# BW1092_LEVEL_SHIFT.net
KiCad netlist of a schematic drawn in Altium Designer
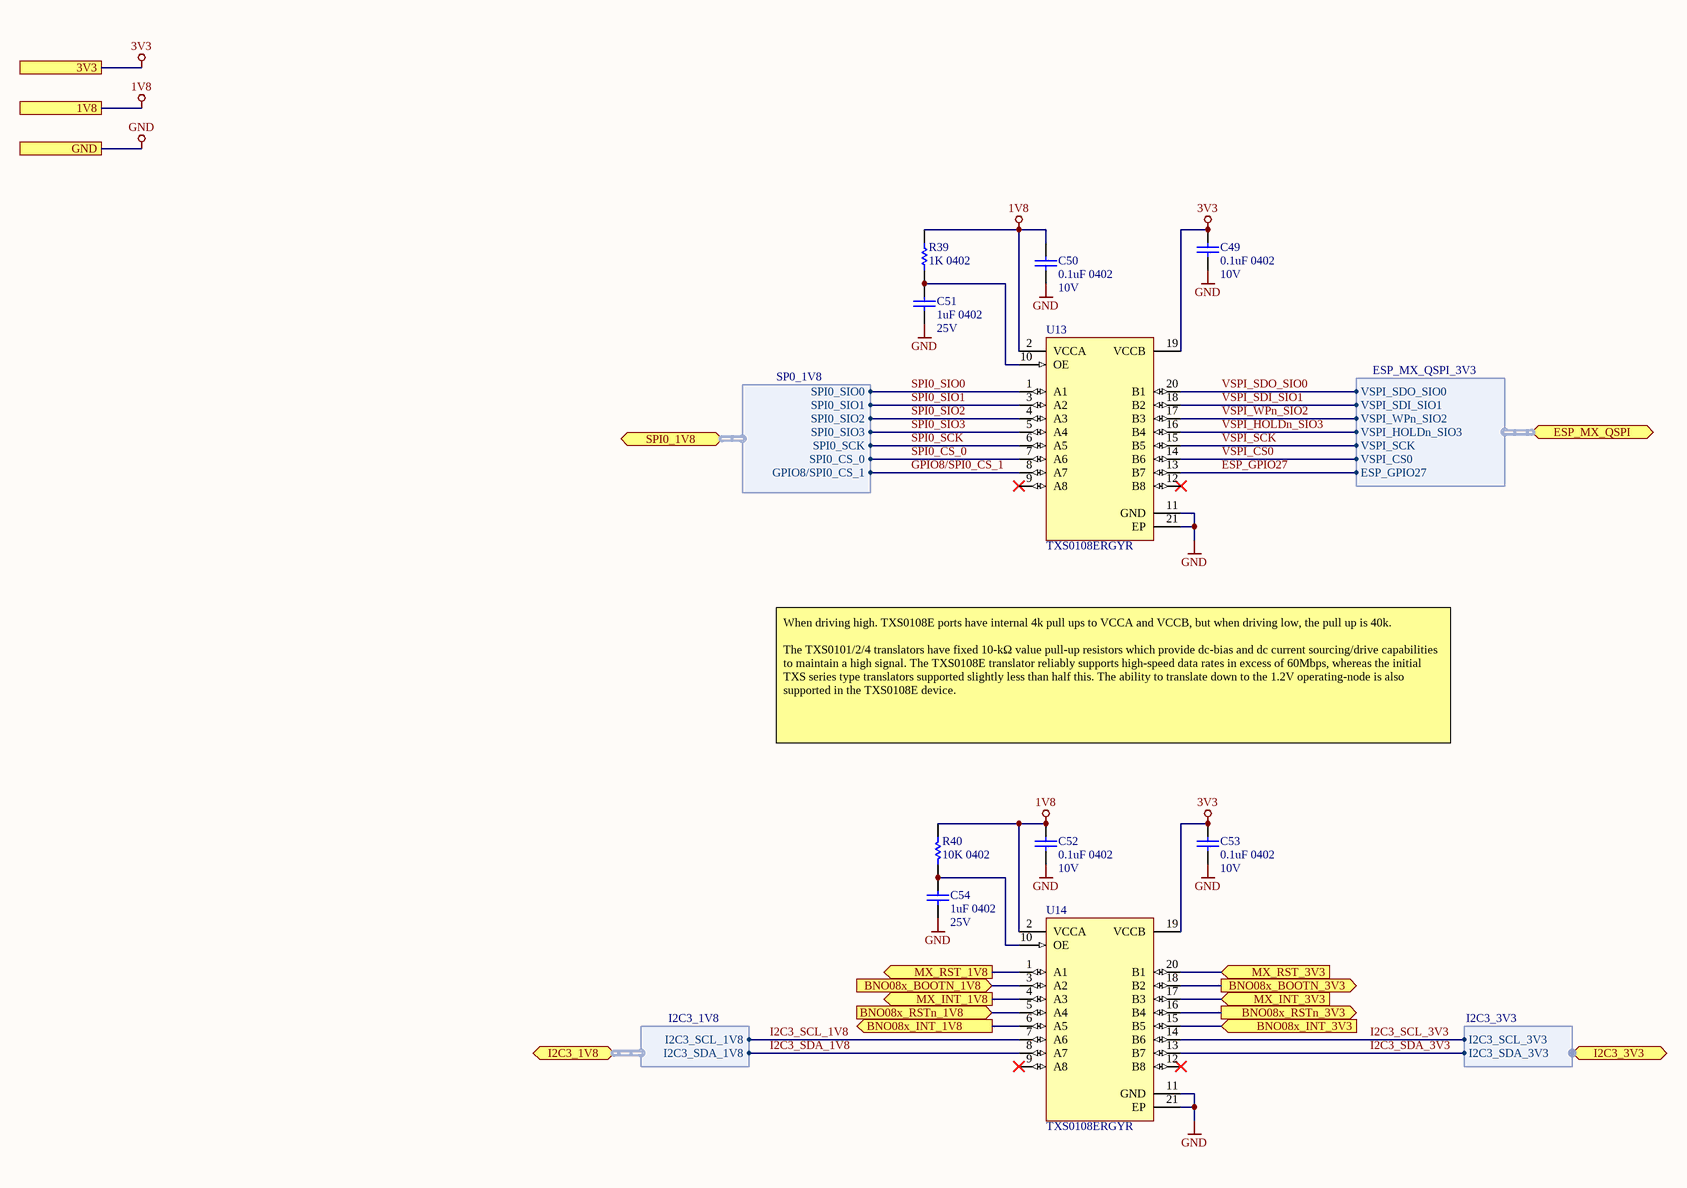
[diagram p0: BW1092_LEVEL_SHIFT.SchDoc]

(export (version "E")
  (design (tool "Eeschema 10.0.6"))
  (components
    (comp (ref "C49")
      (value "0.1uF 0402")
      (footprint "CAP_Altium_Vault_Generic:CAPC0402(1005)70_N")
      (description "CAP CER 0.1UF 10V X7R 0402 5%")
      (fields (field (name "TOLERANCE") "5%") (field (name "VOLTAGE RATING") "10V"))
      (libsource (lib "LuxonisMaster") (part "GRM155R71A104JA01D"))
    )
    (comp (ref "C50")
      (value "0.1uF 0402")
      (footprint "CAP_Altium_Vault_Generic:CAPC0402(1005)70_N")
      (description "CAP CER 0.1UF 10V X7R 0402 5%")
      (fields (field (name "TOLERANCE") "5%") (field (name "VOLTAGE RATING") "10V"))
      (libsource (lib "LuxonisMaster") (part "GRM155R71A104JA01D"))
    )
    (comp (ref "C51")
      (value "1uF 0402")
      (footprint "CAP_Altium_Vault_Generic:CAPC0402(1005)70_N")
      (description "CAP CER 1UF 25V X5R 0402 10%")
      (fields
        (field (name "TOLERANCE") "10%")
        (field (name "VOLTAGE") "25V")
        (field (name "VOLTAGE RATING") "25V")
      )
      (libsource (lib "LuxonisMaster") (part "GRM155R61E105KA12D"))
    )
    (comp (ref "C52")
      (value "0.1uF 0402")
      (footprint "CAP_Altium_Vault_Generic:CAPC0402(1005)70_N")
      (description "CAP CER 0.1UF 10V X7R 0402 5%")
      (fields (field (name "TOLERANCE") "5%") (field (name "VOLTAGE RATING") "10V"))
      (libsource (lib "LuxonisMaster") (part "GRM155R71A104JA01D"))
    )
    (comp (ref "C53")
      (value "0.1uF 0402")
      (footprint "CAP_Altium_Vault_Generic:CAPC0402(1005)70_N")
      (description "CAP CER 0.1UF 10V X7R 0402 5%")
      (fields (field (name "TOLERANCE") "5%") (field (name "VOLTAGE RATING") "10V"))
      (libsource (lib "LuxonisMaster") (part "GRM155R71A104JA01D"))
    )
    (comp (ref "C54")
      (value "1uF 0402")
      (footprint "CAP_Altium_Vault_Generic:CAPC0402(1005)70_N")
      (description "CAP CER 1UF 25V X5R 0402 10%")
      (fields
        (field (name "TOLERANCE") "10%")
        (field (name "VOLTAGE") "25V")
        (field (name "VOLTAGE RATING") "25V")
      )
      (libsource (lib "LuxonisMaster") (part "GRM155R61E105KA12D"))
    )
    (comp (ref "R39")
      (value "1K 0402")
      (footprint "RES_Altium_Vault_Generic:RESC0402(1005)_N")
      (fields (field (name "TOLERANCE") "1%"))
      (libsource (lib "LuxonisMaster") (part "RC0402FR-071KL"))
    )
    (comp (ref "R40")
      (value "10K 0402")
      (footprint "RES_Altium_Vault_Generic:RESC0402(1005)_N")
      (fields (field (name "TOLERANCE") "1%"))
      (libsource (lib "LuxonisMaster") (part "RC0402FR-1310KL"))
    )
    (comp (ref "U13")
      (value "TXS0108ERGYR")
      (footprint "BW1092_R0M0E0:TXS0108ERGYR")
      (description "IC TRNSLTR BIDIRECTIONAL 20VQFN")
      (libsource (lib "BW1092_R0M0E0") (part "TXS0108ERGYR"))
    )
    (comp (ref "U14")
      (value "TXS0108ERGYR")
      (footprint "BW1092_R0M0E0:TXS0108ERGYR")
      (description "IC TRNSLTR BIDIRECTIONAL 20VQFN")
      (libsource (lib "BW1092_R0M0E0") (part "TXS0108ERGYR"))
    )
  )
  (nets
    (net (code "5") (name "/BNO08x_BOOTN_1V8") (class "Default")
      (node (ref "U14") (pin "3") (pinfunction "A2_3") (pintype "bidirectional"))
    )
    (net (code "6") (name "/BNO08x_BOOTN_3V3") (class "Default")
      (node (ref "U14") (pin "18") (pinfunction "B2_18") (pintype "bidirectional"))
    )
    (net (code "7") (name "/BNO08x_INT_1V8") (class "Default")
      (node (ref "U14") (pin "6") (pinfunction "A5_6") (pintype "bidirectional"))
    )
    (net (code "8") (name "/BNO08x_INT_3V3") (class "Default")
      (node (ref "U14") (pin "15") (pinfunction "B5_15") (pintype "bidirectional"))
    )
    (net (code "9") (name "/BNO08x_RSTn_1V8") (class "Default")
      (node (ref "U14") (pin "5") (pinfunction "A4_5") (pintype "bidirectional"))
    )
    (net (code "10") (name "/BNO08x_RSTn_3V3") (class "Default")
      (node (ref "U14") (pin "16") (pinfunction "B4_16") (pintype "bidirectional"))
    )
    (net (code "11") (name "/ESP_GPIO27") (class "Default")
      (node (ref "U13") (pin "13") (pinfunction "B7_13") (pintype "bidirectional"))
    )
    (net (code "12") (name "/GPIO8{slash}SPI0_CS_1") (class "Default")
      (node (ref "U13") (pin "8") (pinfunction "A7_8") (pintype "bidirectional"))
    )
    (net (code "13") (name "/I2C3_SCL_1V8") (class "Default")
      (node (ref "U14") (pin "7") (pinfunction "A6_7") (pintype "bidirectional"))
    )
    (net (code "14") (name "/I2C3_SCL_3V3") (class "Default")
      (node (ref "U14") (pin "14") (pinfunction "B6_14") (pintype "bidirectional"))
    )
    (net (code "15") (name "/I2C3_SDA_1V8") (class "Default")
      (node (ref "U14") (pin "8") (pinfunction "A7_8") (pintype "bidirectional"))
    )
    (net (code "16") (name "/I2C3_SDA_3V3") (class "Default")
      (node (ref "U14") (pin "13") (pinfunction "B7_13") (pintype "bidirectional"))
    )
    (net (code "17") (name "/MX_INT_1V8") (class "Default")
      (node (ref "U14") (pin "4") (pinfunction "A3_4") (pintype "bidirectional"))
    )
    (net (code "18") (name "/MX_INT_3V3") (class "Default")
      (node (ref "U14") (pin "17") (pinfunction "B3_17") (pintype "bidirectional"))
    )
    (net (code "19") (name "/MX_RST_1V8") (class "Default")
      (node (ref "U14") (pin "1") (pinfunction "A1_1") (pintype "bidirectional"))
    )
    (net (code "20") (name "/MX_RST_3V3") (class "Default")
      (node (ref "U14") (pin "20") (pinfunction "B1_20") (pintype "bidirectional"))
    )
    (net (code "21") (name "/SPI0_CS_0") (class "Default")
      (node (ref "U13") (pin "7") (pinfunction "A6_7") (pintype "bidirectional"))
    )
    (net (code "22") (name "/SPI0_SCK") (class "Default")
      (node (ref "U13") (pin "6") (pinfunction "A5_6") (pintype "bidirectional"))
    )
    (net (code "23") (name "/SPI0_SIO0") (class "Default")
      (node (ref "U13") (pin "1") (pinfunction "A1_1") (pintype "bidirectional"))
    )
    (net (code "24") (name "/SPI0_SIO1") (class "Default")
      (node (ref "U13") (pin "3") (pinfunction "A2_3") (pintype "bidirectional"))
    )
    (net (code "25") (name "/SPI0_SIO2") (class "Default")
      (node (ref "U13") (pin "4") (pinfunction "A3_4") (pintype "bidirectional"))
    )
    (net (code "26") (name "/SPI0_SIO3") (class "Default")
      (node (ref "U13") (pin "5") (pinfunction "A4_5") (pintype "bidirectional"))
    )
    (net (code "27") (name "/VSPI_CS0") (class "Default")
      (node (ref "U13") (pin "14") (pinfunction "B6_14") (pintype "bidirectional"))
    )
    (net (code "28") (name "/VSPI_HOLDn_SIO3") (class "Default")
      (node (ref "U13") (pin "16") (pinfunction "B4_16") (pintype "bidirectional"))
    )
    (net (code "29") (name "/VSPI_SCK") (class "Default")
      (node (ref "U13") (pin "15") (pinfunction "B5_15") (pintype "bidirectional"))
    )
    (net (code "30") (name "/VSPI_SDI_SIO1") (class "Default")
      (node (ref "U13") (pin "18") (pinfunction "B2_18") (pintype "bidirectional"))
    )
    (net (code "31") (name "/VSPI_SDO_SIO0") (class "Default")
      (node (ref "U13") (pin "20") (pinfunction "B1_20") (pintype "bidirectional"))
    )
    (net (code "32") (name "/VSPI_WPn_SIO2") (class "Default")
      (node (ref "U13") (pin "17") (pinfunction "B3_17") (pintype "bidirectional"))
    )
    (net (code "37") (name "1V8") (class "Default")
      (node (ref "C50") (pin "2") (pinfunction "2_2") (pintype "passive"))
      (node (ref "C52") (pin "2") (pinfunction "2_2") (pintype "passive"))
      (node (ref "R39") (pin "2") (pinfunction "2_2") (pintype "passive"))
      (node (ref "R40") (pin "1") (pinfunction "1_1") (pintype "passive"))
      (node (ref "U13") (pin "2") (pinfunction "VCCA_2") (pintype "power_in"))
      (node (ref "U14") (pin "2") (pinfunction "VCCA_2") (pintype "power_in"))
    )
    (net (code "38") (name "3V3") (class "Default")
      (node (ref "C49") (pin "2") (pinfunction "2_2") (pintype "passive"))
      (node (ref "C53") (pin "2") (pinfunction "2_2") (pintype "passive"))
      (node (ref "U13") (pin "19") (pinfunction "VCCB_19") (pintype "power_in"))
      (node (ref "U14") (pin "19") (pinfunction "VCCB_19") (pintype "power_in"))
    )
    (net (code "39") (name "GND") (class "Default")
      (node (ref "C49") (pin "1") (pinfunction "1_1") (pintype "passive"))
      (node (ref "C50") (pin "1") (pinfunction "1_1") (pintype "passive"))
      (node (ref "C51") (pin "1") (pinfunction "1_1") (pintype "passive"))
      (node (ref "C52") (pin "1") (pinfunction "1_1") (pintype "passive"))
      (node (ref "C53") (pin "1") (pinfunction "1_1") (pintype "passive"))
      (node (ref "C54") (pin "1") (pinfunction "1_1") (pintype "passive"))
      (node (ref "U13") (pin "11") (pinfunction "GND_11") (pintype "power_in"))
      (node (ref "U13") (pin "21") (pinfunction "EP_21") (pintype "power_in"))
      (node (ref "U14") (pin "11") (pinfunction "GND_11") (pintype "power_in"))
      (node (ref "U14") (pin "21") (pinfunction "EP_21") (pintype "power_in"))
    )
    (net (code "40") (name "Net-(U13-OE)") (class "Default")
      (node (ref "C51") (pin "2") (pinfunction "2_2") (pintype "passive"))
      (node (ref "R39") (pin "1") (pinfunction "1_1") (pintype "passive"))
      (node (ref "U13") (pin "10") (pinfunction "OE_10") (pintype "input"))
    )
    (net (code "41") (name "Net-(U14-OE)") (class "Default")
      (node (ref "C54") (pin "2") (pinfunction "2_2") (pintype "passive"))
      (node (ref "R40") (pin "2") (pinfunction "2_2") (pintype "passive"))
      (node (ref "U14") (pin "10") (pinfunction "OE_10") (pintype "input"))
    )
    (net (code "42") (name "unconnected-(U13-A8-Pad9)") (class "Default")
      (node (ref "U13") (pin "9") (pinfunction "A8_9") (pintype "bidirectional+no_connect"))
    )
    (net (code "43") (name "unconnected-(U13-B8-Pad12)") (class "Default")
      (node (ref "U13") (pin "12") (pinfunction "B8_12") (pintype "bidirectional+no_connect"))
    )
    (net (code "44") (name "unconnected-(U14-A8-Pad9)") (class "Default")
      (node (ref "U14") (pin "9") (pinfunction "A8_9") (pintype "bidirectional+no_connect"))
    )
    (net (code "45") (name "unconnected-(U14-B8-Pad12)") (class "Default")
      (node (ref "U14") (pin "12") (pinfunction "B8_12") (pintype "bidirectional+no_connect"))
    )
  )
)
